# InkTime_NAN.net
KiCad netlist of a schematic drawn in EAGLE
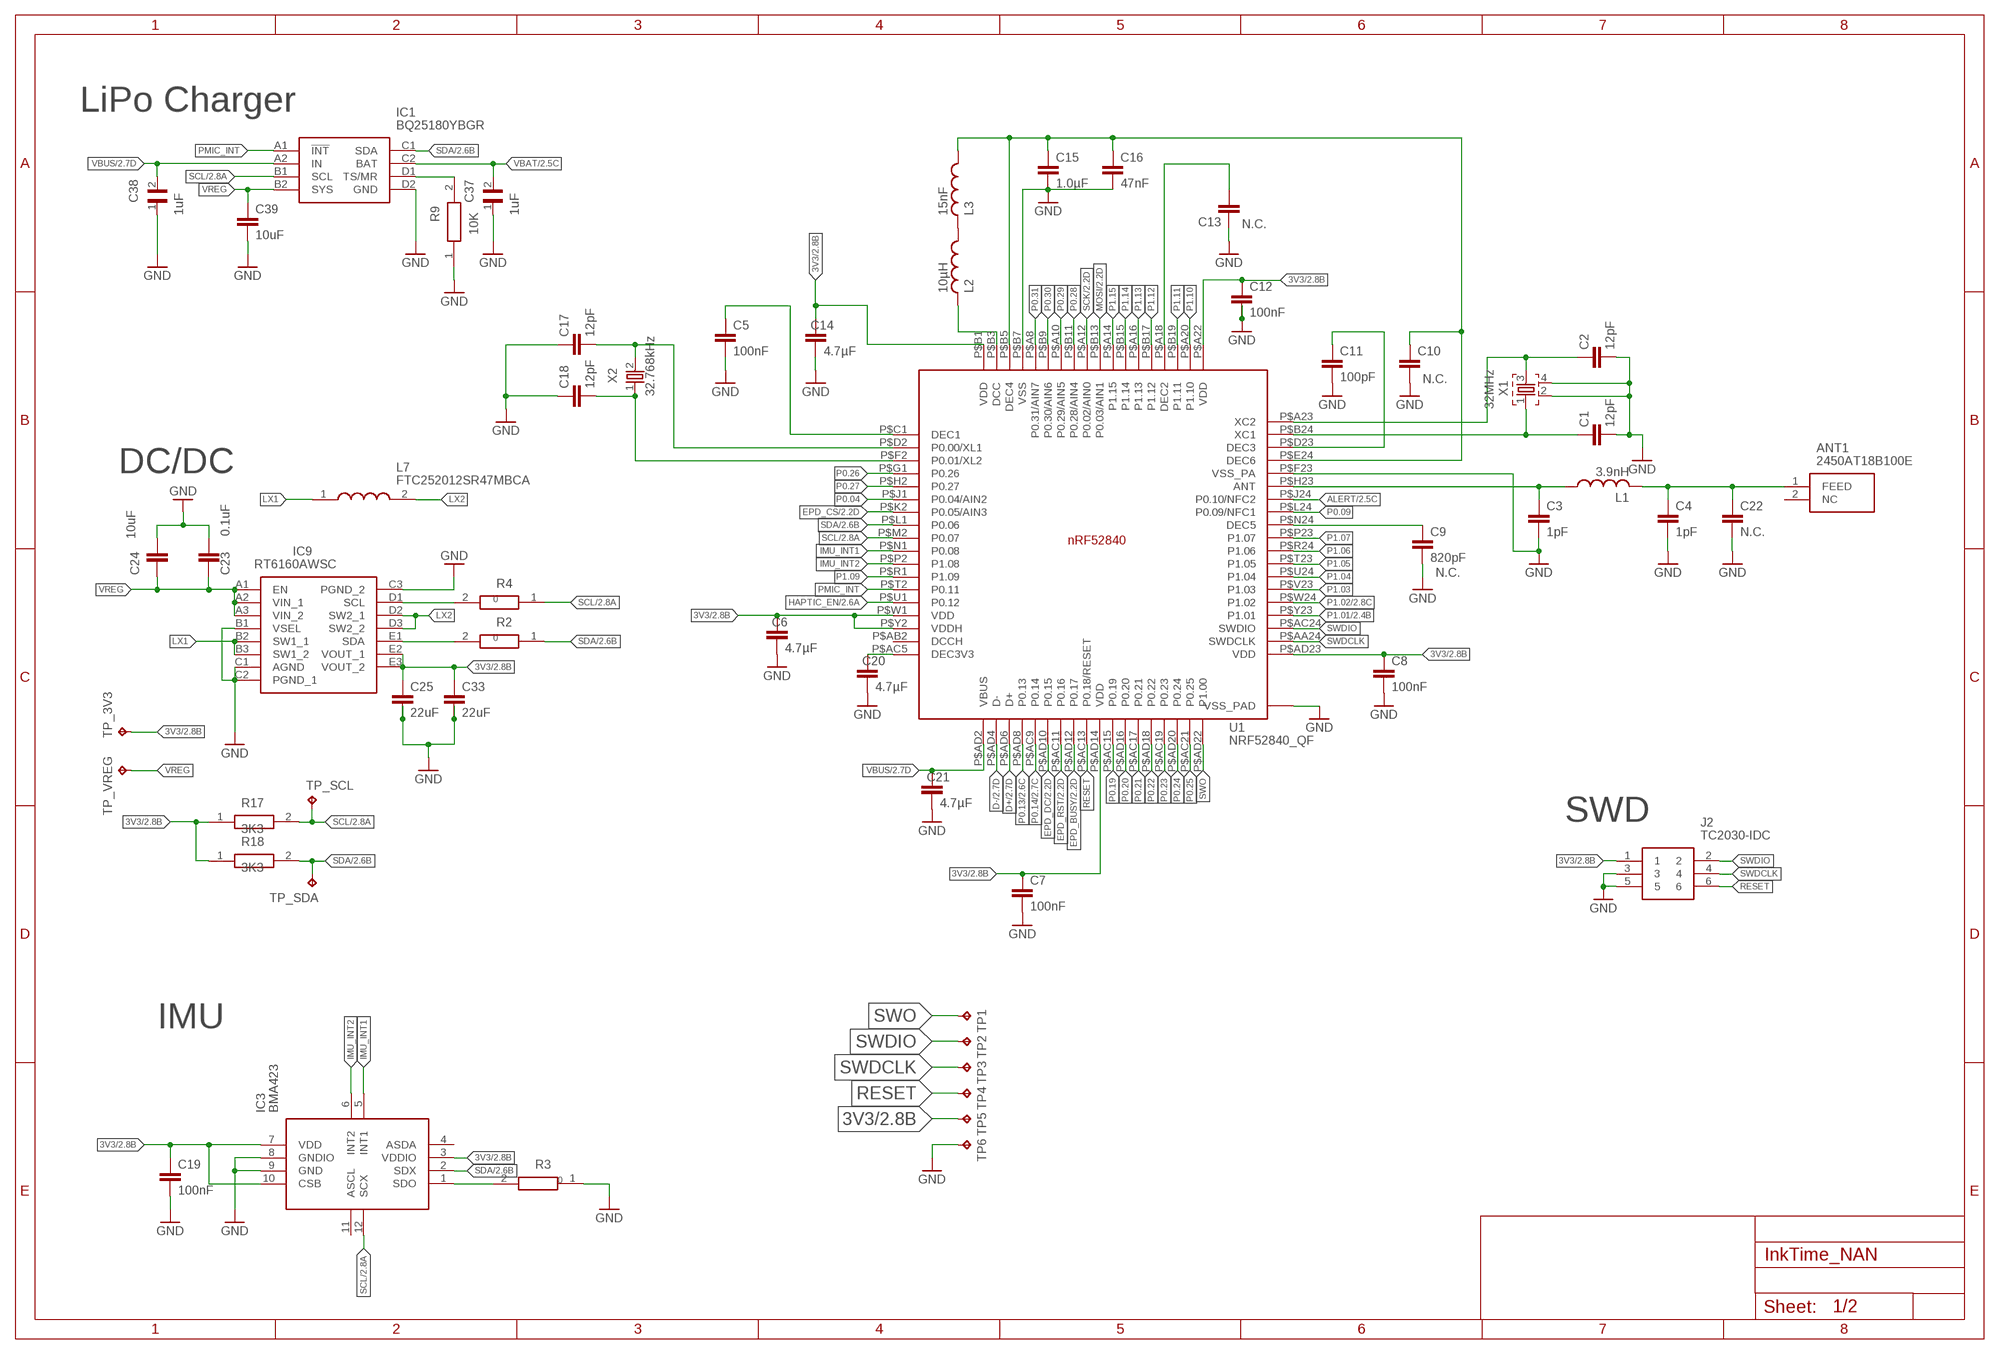
[diagram p0: schematic, sheet 1]
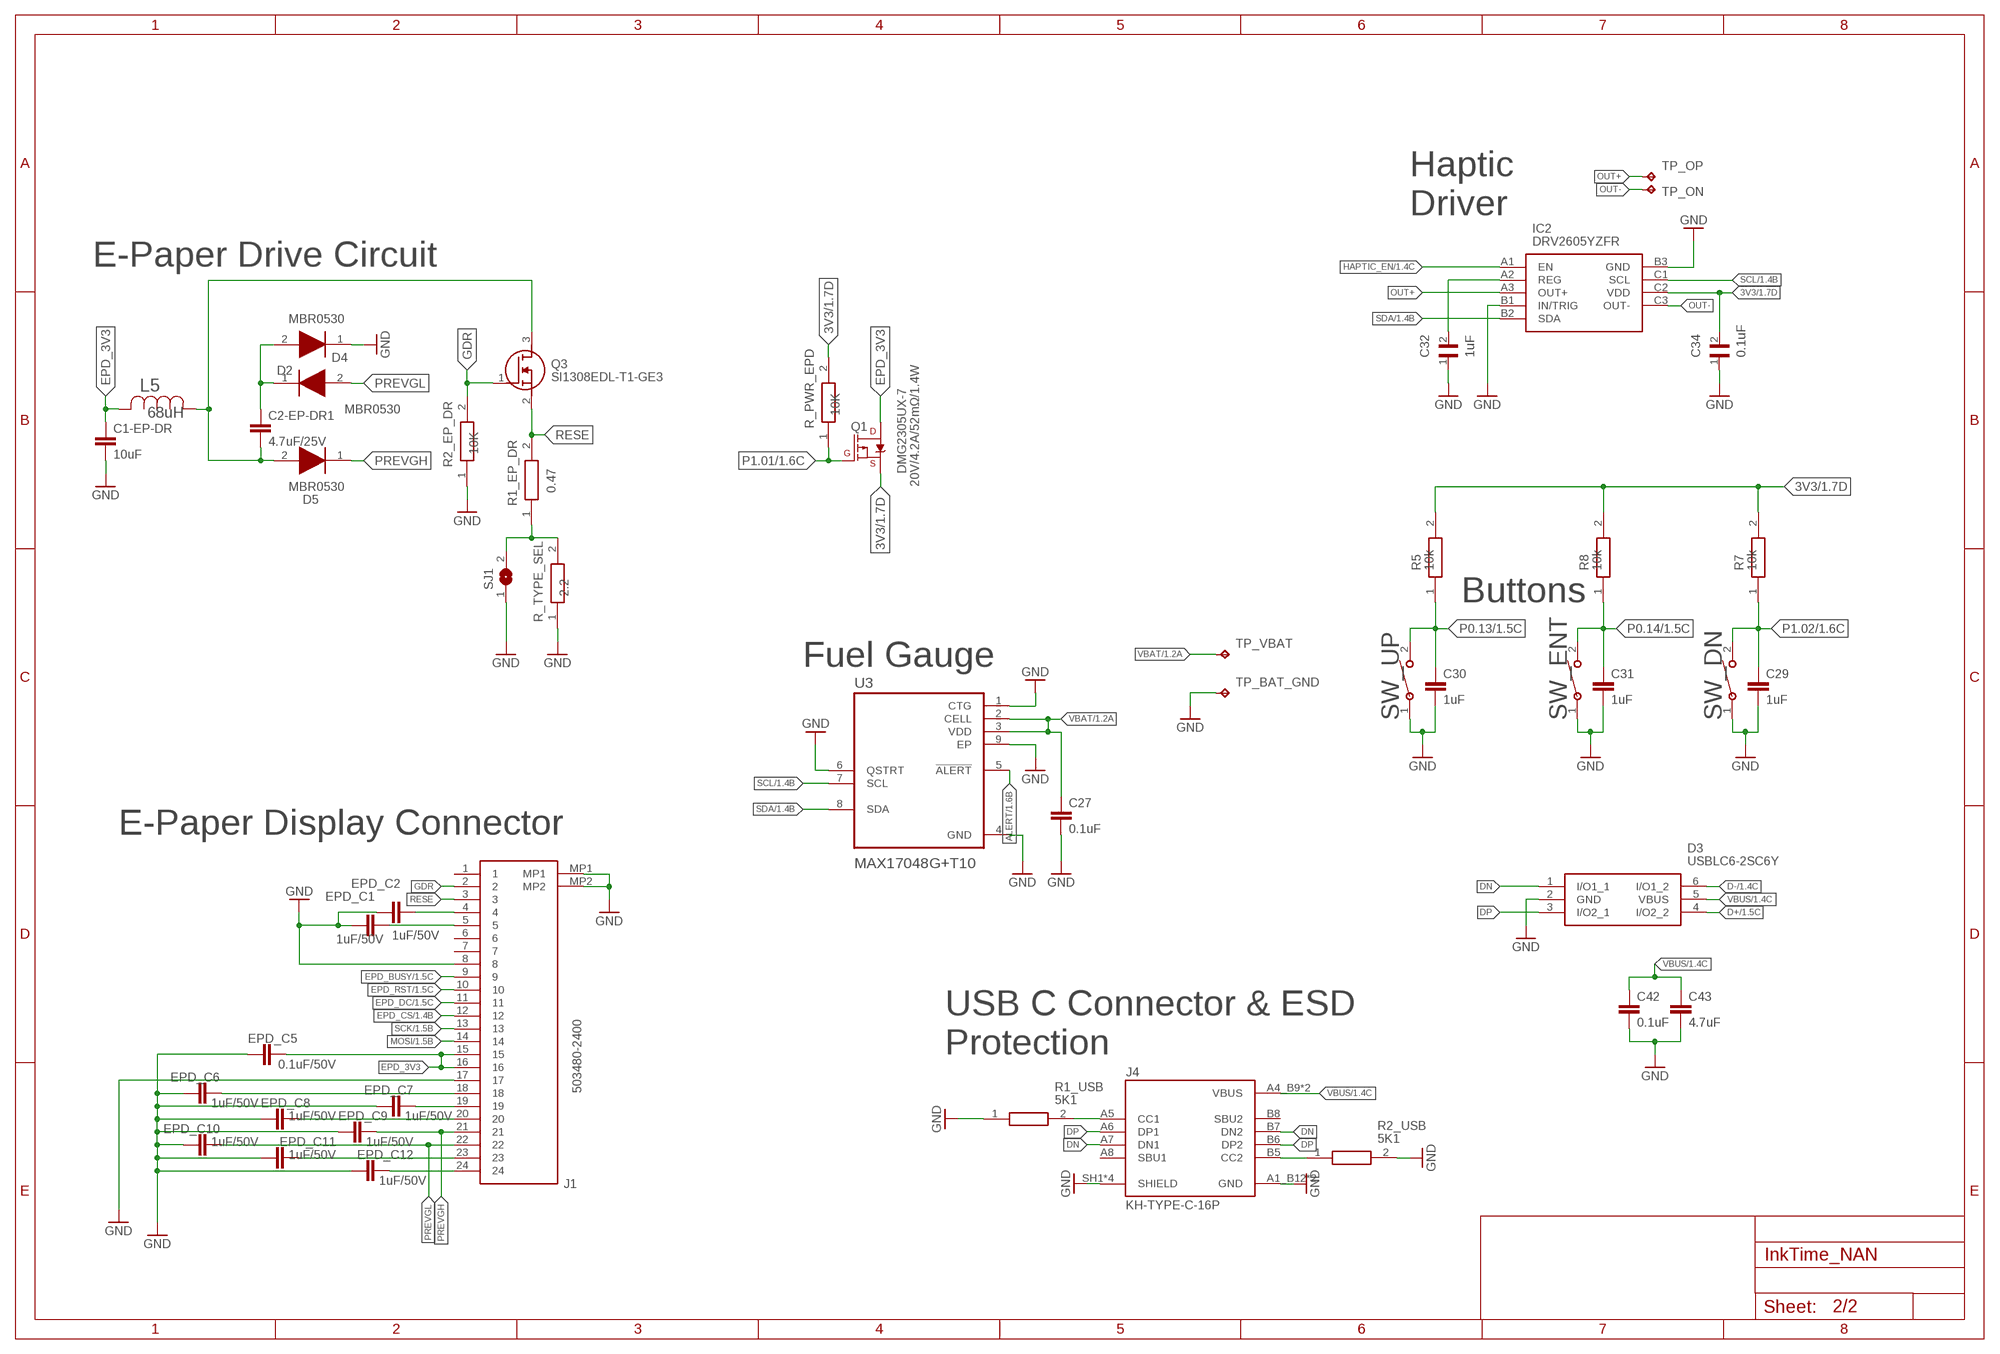
[diagram p1: schematic, sheet 2]

(export (version "E")
  (design (tool "Eeschema 10.0.6"))
  (components
    (comp (ref "C1-EP-DR")
      (value "10uF")
      (footprint "eagle-import:NORDIC_NRF_3_RESC0402_L")
      (libsource (lib "eagle-import") (part "NORDIC_NRF_3_CAPACITOR_0402_L"))
    )
    (comp (ref "C2-EP-DR1")
      (value "4.7uF/25V")
      (footprint "eagle-import:NORDIC_NRF_3_RESC0402_L")
      (libsource (lib "eagle-import") (part "NORDIC_NRF_3_CAPACITOR_0402_L"))
    )
    (comp (ref "C27")
      (value "0.1uF")
      (footprint "eagle-import:NORDIC_NRF_3_RESC0201_L")
      (libsource (lib "eagle-import") (part "NORDIC_NRF_3_CAPACITOR_0201_L"))
    )
    (comp (ref "C29")
      (value "1uF")
      (footprint "eagle-import:NORDIC_NRF_3_RESC0402_L")
      (libsource (lib "eagle-import") (part "NORDIC_NRF_3_CAPACITOR_0402_L"))
    )
    (comp (ref "C30")
      (value "1uF")
      (footprint "eagle-import:NORDIC_NRF_3_RESC0402_L")
      (libsource (lib "eagle-import") (part "NORDIC_NRF_3_CAPACITOR_0402_L"))
    )
    (comp (ref "C31")
      (value "1uF")
      (footprint "eagle-import:NORDIC_NRF_3_RESC0402_L")
      (libsource (lib "eagle-import") (part "NORDIC_NRF_3_CAPACITOR_0402_L"))
    )
    (comp (ref "C32")
      (value "1uF")
      (footprint "eagle-import:GRM011R60J152KE01L_2_CAPC0201X13N")
      (fields (field (name "MF") "Murata") (field (name "MP") "GRM011R60J152KE01L"))
      (libsource (lib "eagle-import") (part "GRM011R60J152KE01L_2_GRM011R60J152KE01L"))
    )
    (comp (ref "C34")
      (value "0.1uF")
      (footprint "eagle-import:GRM011R60J152KE01L_2_CAPC0201X13N")
      (fields (field (name "MF") "Murata") (field (name "MP") "GRM011R60J152KE01L"))
      (libsource (lib "eagle-import") (part "GRM011R60J152KE01L_2_GRM011R60J152KE01L"))
    )
    (comp (ref "C42")
      (value "0.1uF")
      (footprint "eagle-import:NORDIC_NRF_3_RESC0201_L")
      (libsource (lib "eagle-import") (part "NORDIC_NRF_3_CAPACITOR_0201_L"))
    )
    (comp (ref "C43")
      (value "4.7uF")
      (footprint "eagle-import:NORDIC_NRF_3_RESC0402_L")
      (libsource (lib "eagle-import") (part "NORDIC_NRF_3_CAPACITOR_0402_L"))
    )
    (comp (ref "D2")
      (value "MBR0530")
      (footprint "eagle-import:ESP32_C6_LIBRARY_5_SOD3716X135N")
      (fields (field (name "MF") "ON Semiconductor"))
      (libsource (lib "eagle-import") (part "ESP32_C6_LIBRARY_5_MBR0530"))
    )
    (comp (ref "D3")
      (value "USBLC6-2SC6Y")
      (footprint "eagle-import:ESP32_C6_LIBRARY_3_SOT95P280X145-6N")
      (fields (field (name "MF") "STMicroelectronics"))
      (libsource (lib "eagle-import") (part "ESP32_C6_LIBRARY_3_USBLC6-2SC6Y"))
    )
    (comp (ref "D4")
      (value "MBR0530")
      (footprint "eagle-import:ESP32_C6_LIBRARY_5_SOD3716X135N")
      (fields (field (name "MF") "ON Semiconductor"))
      (libsource (lib "eagle-import") (part "ESP32_C6_LIBRARY_5_MBR0530"))
    )
    (comp (ref "D5")
      (value "MBR0530")
      (footprint "eagle-import:ESP32_C6_LIBRARY_5_SOD3716X135N")
      (fields (field (name "MF") "ON Semiconductor"))
      (libsource (lib "eagle-import") (part "ESP32_C6_LIBRARY_5_MBR0530"))
    )
    (comp (ref "EPD_C1")
      (value "1uF/50V")
      (footprint "eagle-import:NORDIC_NRF_3_RESC0402_L")
      (libsource (lib "eagle-import") (part "NORDIC_NRF_3_CAPACITOR_0402_L"))
    )
    (comp (ref "EPD_C2")
      (value "1uF/50V")
      (footprint "eagle-import:NORDIC_NRF_3_RESC0402_L")
      (libsource (lib "eagle-import") (part "NORDIC_NRF_3_CAPACITOR_0402_L"))
    )
    (comp (ref "EPD_C5")
      (value "0.1uF/50V")
      (footprint "eagle-import:NORDIC_NRF_3_RESC0201_L")
      (libsource (lib "eagle-import") (part "NORDIC_NRF_3_CAPACITOR_0201_L"))
    )
    (comp (ref "EPD_C6")
      (value "1uF/50V")
      (footprint "eagle-import:NORDIC_NRF_3_RESC0402_L")
      (libsource (lib "eagle-import") (part "NORDIC_NRF_3_CAPACITOR_0402_L"))
    )
    (comp (ref "EPD_C7")
      (value "1uF/50V")
      (footprint "eagle-import:NORDIC_NRF_3_RESC0402_L")
      (libsource (lib "eagle-import") (part "NORDIC_NRF_3_CAPACITOR_0402_L"))
    )
    (comp (ref "EPD_C8")
      (value "1uF/50V")
      (footprint "eagle-import:NORDIC_NRF_3_RESC0402_L")
      (libsource (lib "eagle-import") (part "NORDIC_NRF_3_CAPACITOR_0402_L"))
    )
    (comp (ref "EPD_C9")
      (value "1uF/50V")
      (footprint "eagle-import:NORDIC_NRF_3_RESC0402_L")
      (libsource (lib "eagle-import") (part "NORDIC_NRF_3_CAPACITOR_0402_L"))
    )
    (comp (ref "EPD_C10")
      (value "1uF/50V")
      (footprint "eagle-import:NORDIC_NRF_3_RESC0402_L")
      (libsource (lib "eagle-import") (part "NORDIC_NRF_3_CAPACITOR_0402_L"))
    )
    (comp (ref "EPD_C11")
      (value "1uF/50V")
      (footprint "eagle-import:NORDIC_NRF_3_RESC0402_L")
      (libsource (lib "eagle-import") (part "NORDIC_NRF_3_CAPACITOR_0402_L"))
    )
    (comp (ref "EPD_C12")
      (value "1uF/50V")
      (footprint "eagle-import:NORDIC_NRF_3_RESC0402_L")
      (libsource (lib "eagle-import") (part "NORDIC_NRF_3_CAPACITOR_0402_L"))
    )
    (comp (ref "IC2")
      (value "DRV2605YZFR")
      (footprint "eagle-import:DRV2605YZFR_BGA9C50P3X3_144X144X62")
      (libsource (lib "eagle-import") (part "DRV2605YZFR_DRV2605YZFR"))
    )
    (comp (ref "J1")
      (value "503480-2400")
      (footprint "eagle-import:503480-2400_5034802400")
      (fields (field (name "MOUSER_PART_NUMBER") "538-503480-2400"))
      (libsource (lib "eagle-import") (part "503480-2400_503480-2400"))
    )
    (comp (ref "J4")
      (value "KH-TYPE-C-16P")
      (footprint "eagle-import:KH-TYPE-C-16P_KINGHELM_KH-TYPE-C-16P")
      (fields (field (name "MF") "kinghelm"))
      (libsource (lib "eagle-import") (part "KH-TYPE-C-16P_KH-TYPE-C-16P"))
    )
    (comp (ref "L5")
      (value "68uH")
      (footprint "eagle-import:ESP32_C6_LIBRARY_2_IND_4828-WE-TPC_WRE")
      (fields
        (field (name "MANUFACTURER_PART_NUMBER") "744043680")
        (field (name "COPYRIGHT") "Copyright (C) 2024 Ultra Librarian. All rights reserved.")
      )
      (libsource (lib "eagle-import") (part "ESP32_C6_LIBRARY_2_744043680IND_4828-WE-TPC_WRE"))
    )
    (comp (ref "Q1")
      (value "20V/4.2A/52mΩ/1.4W")
      (footprint "eagle-import:ESP32_C6_LIBRARY_4_ESP32_C6_LIBRARY_4_ESP32_C6_LIBRARY_4_ESP32_C6_LIBRARY_4_ESP32_WROVER_SPARKFUN-DISCRETESEMI_SOT23-3")
      (libsource (lib "eagle-import") (part "ESP32_C6_LIBRARY_4_ESP32_WROVER_SPARKFUN-DISCRETESEMI_MOSFET_PCH-DMG2305UX-7"))
    )
    (comp (ref "Q3")
      (value "SI1308EDL-T1-GE3")
      (footprint "eagle-import:ESP32_C6_LIBRARY_6_SOT65P210X110-3N")
      (fields (field (name "MF") "Vishay Siliconix"))
      (libsource (lib "eagle-import") (part "ESP32_C6_LIBRARY_6_SI1308EDL-T1-GE3"))
    )
    (comp (ref "R1_EP_DR")
      (value "0.47")
      (footprint "eagle-import:CPF0201D7K68C1_0201")
      (libsource (lib "eagle-import") (part "CPF0201D7K68C1_CPF0201D7K68C1"))
    )
    (comp (ref "R1_USB")
      (value "5K1")
      (footprint "eagle-import:ERA-1AEB3401C_0201")
      (libsource (lib "eagle-import") (part "ERA-1AEB3401C_CPF0201D7K68C1"))
    )
    (comp (ref "R2_EP_DR")
      (value "10K")
      (footprint "eagle-import:CPF0201D7K68C1_0201")
      (libsource (lib "eagle-import") (part "CPF0201D7K68C1_CPF0201D7K68C1"))
    )
    (comp (ref "R2_USB")
      (value "5K1")
      (footprint "eagle-import:ERA-1AEB3401C_0201")
      (libsource (lib "eagle-import") (part "ERA-1AEB3401C_CPF0201D7K68C1"))
    )
    (comp (ref "R5")
      (value "10k")
      (footprint "eagle-import:CPF0201D7K68C1_0201")
      (libsource (lib "eagle-import") (part "CPF0201D7K68C1_CPF0201D7K68C1"))
    )
    (comp (ref "R7")
      (value "10k")
      (footprint "eagle-import:CPF0201D7K68C1_0201")
      (libsource (lib "eagle-import") (part "CPF0201D7K68C1_CPF0201D7K68C1"))
    )
    (comp (ref "R8")
      (value "10k")
      (footprint "eagle-import:CPF0201D7K68C1_0201")
      (libsource (lib "eagle-import") (part "CPF0201D7K68C1_CPF0201D7K68C1"))
    )
    (comp (ref "R_PWR_EPD")
      (value "10K")
      (footprint "eagle-import:CPF0201D7K68C1_0201")
      (libsource (lib "eagle-import") (part "CPF0201D7K68C1_CPF0201D7K68C1"))
    )
    (comp (ref "R_TYPE_SEL")
      (value "2.2")
      (footprint "eagle-import:CPF0201D7K68C1_0201")
      (libsource (lib "eagle-import") (part "CPF0201D7K68C1_CPF0201D7K68C1"))
    )
    (comp (ref "SJ1")
      (value "ESP32_C6_LIBRARY_7_JUMPER_SJ")
      (footprint "eagle-import:ESP32_C6_LIBRARY_7_JUMPER_SJ")
      (libsource (lib "eagle-import") (part "ESP32_C6_LIBRARY_7_JUMPER_SJ"))
    )
    (comp (ref "SW_DN")
      (value "2025-10-22_07-23-44_LIBRARY_EVP-AKE31ASW_EVP-AKE31A_PAN")
      (footprint "eagle-import:2025-10-22_07-23-44_LIBRARY_SW_EVP-AKE31A_PAN")
      (fields
        (field (name "MANUFACTURER_PART_NUMBER") "EVP-AKE31A")
        (field (name "COPYRIGHT") "Copyright (C) 2025 Ultra Librarian. All rights reserved.")
      )
      (libsource (lib "eagle-import") (part "2025-10-22_07-23-44_LIBRARY_EVP-AKE31ASW_EVP-AKE31A_PAN"))
    )
    (comp (ref "SW_ENT")
      (value "SW_ENT")
      (footprint "eagle-import:2025-10-22_07-23-44_LIBRARY_SW_EVP-AKE31A_PAN")
      (fields
        (field (name "MANUFACTURER_PART_NUMBER") "EVP-AKE31A")
        (field (name "COPYRIGHT") "Copyright (C) 2025 Ultra Librarian. All rights reserved.")
      )
      (libsource (lib "eagle-import") (part "2025-10-22_07-23-44_LIBRARY_EVP-AKE31ASW_EVP-AKE31A_PAN"))
    )
    (comp (ref "SW_UP")
      (value "2025-10-22_07-23-44_LIBRARY_EVP-AKE31ASW_EVP-AKE31A_PAN")
      (footprint "eagle-import:2025-10-22_07-23-44_LIBRARY_SW_EVP-AKE31A_PAN")
      (fields
        (field (name "MANUFACTURER_PART_NUMBER") "EVP-AKE31A")
        (field (name "COPYRIGHT") "Copyright (C) 2025 Ultra Librarian. All rights reserved.")
      )
      (libsource (lib "eagle-import") (part "2025-10-22_07-23-44_LIBRARY_EVP-AKE31ASW_EVP-AKE31A_PAN"))
    )
    (comp (ref "TP_BAT_GND")
      (value "HECTOR_WATCH_1_TPTP20R")
      (footprint "eagle-import:HECTOR_WATCH_1_TP20R")
      (libsource (lib "eagle-import") (part "HECTOR_WATCH_1_TPTP20R"))
    )
    (comp (ref "TP_ON")
      (value "HECTOR_WATCH_1_TPTP20R")
      (footprint "eagle-import:HECTOR_WATCH_1_TP20R")
      (libsource (lib "eagle-import") (part "HECTOR_WATCH_1_TPTP20R"))
    )
    (comp (ref "TP_OP")
      (value "HECTOR_WATCH_1_TPTP20R")
      (footprint "eagle-import:HECTOR_WATCH_1_TP20R")
      (libsource (lib "eagle-import") (part "HECTOR_WATCH_1_TPTP20R"))
    )
    (comp (ref "TP_VBAT")
      (value "HECTOR_WATCH_1_TPTP20R")
      (footprint "eagle-import:HECTOR_WATCH_1_TP20R")
      (libsource (lib "eagle-import") (part "HECTOR_WATCH_1_TPTP20R"))
    )
    (comp (ref "U3")
      (value "MAX17048G+T10")
      (footprint "eagle-import:ESP32_C6_LIBRARY_SON50P200X200X80-9N")
      (fields (field (name "MF") "Analog Devices"))
      (libsource (lib "eagle-import") (part "ESP32_C6_LIBRARY_MAX17048G+T10"))
    )
    (comp (ref "ANT1")
      (value "2450AT18B100E")
      (footprint "eagle-import:2450AT18B100E_ANTC3216X140N")
      (fields (field (name "MOUSER_PART_NUMBER") "609-2450AT18B100E"))
      (libsource (lib "eagle-import") (part "2450AT18B100E_2450AT18B100E"))
    )
    (comp (ref "C1")
      (value "12pF")
      (footprint "eagle-import:NORDIC_NRF_3_RESC0201_L")
      (libsource (lib "eagle-import") (part "NORDIC_NRF_3_CAPACITOR_0201_L"))
    )
    (comp (ref "C2")
      (value "12pF")
      (footprint "eagle-import:NORDIC_NRF_3_RESC0201_L")
      (libsource (lib "eagle-import") (part "NORDIC_NRF_3_CAPACITOR_0201_L"))
    )
    (comp (ref "C3")
      (value "1pF")
      (footprint "eagle-import:NORDIC_NRF_3_RESC0201_L")
      (libsource (lib "eagle-import") (part "NORDIC_NRF_3_CAPACITOR_0201_L"))
    )
    (comp (ref "C4")
      (value "1pF")
      (footprint "eagle-import:NORDIC_NRF_3_RESC0201_L")
      (libsource (lib "eagle-import") (part "NORDIC_NRF_3_CAPACITOR_0201_L"))
    )
    (comp (ref "C5")
      (value "100nF")
      (footprint "eagle-import:NORDIC_NRF_3_RESC0201_L")
      (libsource (lib "eagle-import") (part "NORDIC_NRF_3_CAPACITOR_0201_L"))
    )
    (comp (ref "C6")
      (value "4.7µF")
      (footprint "eagle-import:NORDIC_NRF_3_RESC0402_L")
      (libsource (lib "eagle-import") (part "NORDIC_NRF_3_CAPACITOR_0402_L"))
    )
    (comp (ref "C7")
      (value "100nF")
      (footprint "eagle-import:NORDIC_NRF_3_RESC0201_L")
      (libsource (lib "eagle-import") (part "NORDIC_NRF_3_CAPACITOR_0201_L"))
    )
    (comp (ref "C8")
      (value "100nF")
      (footprint "eagle-import:NORDIC_NRF_3_RESC0201_L")
      (libsource (lib "eagle-import") (part "NORDIC_NRF_3_CAPACITOR_0201_L"))
    )
    (comp (ref "C9")
      (value "820pF")
      (footprint "eagle-import:NORDIC_NRF_3_RESC0201_L")
      (libsource (lib "eagle-import") (part "NORDIC_NRF_3_CAPACITOR_0201_L"))
    )
    (comp (ref "C10")
      (value "NORDIC_NRF_3_CAPACITOR_0201_L")
      (footprint "eagle-import:NORDIC_NRF_3_RESC0201_L")
      (libsource (lib "eagle-import") (part "NORDIC_NRF_3_CAPACITOR_0201_L"))
    )
    (comp (ref "C11")
      (value "100pF")
      (footprint "eagle-import:NORDIC_NRF_3_RESC0201_L")
      (libsource (lib "eagle-import") (part "NORDIC_NRF_3_CAPACITOR_0201_L"))
    )
    (comp (ref "C12")
      (value "100nF")
      (footprint "eagle-import:NORDIC_NRF_3_RESC0201_L")
      (libsource (lib "eagle-import") (part "NORDIC_NRF_3_CAPACITOR_0201_L"))
    )
    (comp (ref "C13")
      (value "NORDIC_NRF_3_CAPACITOR_0201_L")
      (footprint "eagle-import:NORDIC_NRF_3_RESC0201_L")
      (libsource (lib "eagle-import") (part "NORDIC_NRF_3_CAPACITOR_0201_L"))
    )
    (comp (ref "C14")
      (value "4.7µF")
      (footprint "eagle-import:NORDIC_NRF_3_RESC0402_L")
      (libsource (lib "eagle-import") (part "NORDIC_NRF_3_CAPACITOR_0402_L"))
    )
    (comp (ref "C15")
      (value "1.0µF")
      (footprint "eagle-import:NORDIC_NRF_3_RESC0402_L")
      (libsource (lib "eagle-import") (part "NORDIC_NRF_3_CAPACITOR_0402_L"))
    )
    (comp (ref "C16")
      (value "47nF")
      (footprint "eagle-import:NORDIC_NRF_3_RESC0201_L")
      (libsource (lib "eagle-import") (part "NORDIC_NRF_3_CAPACITOR_0201_L"))
    )
    (comp (ref "C17")
      (value "12pF")
      (footprint "eagle-import:NORDIC_NRF_3_RESC0201_L")
      (libsource (lib "eagle-import") (part "NORDIC_NRF_3_CAPACITOR_0201_L"))
    )
    (comp (ref "C18")
      (value "12pF")
      (footprint "eagle-import:NORDIC_NRF_3_RESC0201_L")
      (libsource (lib "eagle-import") (part "NORDIC_NRF_3_CAPACITOR_0201_L"))
    )
    (comp (ref "C19")
      (value "100nF")
      (footprint "eagle-import:NORDIC_NRF_3_RESC0201_L")
      (libsource (lib "eagle-import") (part "InkTime_v5_vf.fkz7WSyWSr61TWkXU9X4_w_NORDIC_NRF_3_CAPACITOR_0201_L"))
    )
    (comp (ref "C20")
      (value "4.7µF")
      (footprint "eagle-import:NORDIC_NRF_3_RESC0402_L")
      (libsource (lib "eagle-import") (part "NORDIC_NRF_3_CAPACITOR_0402_L"))
    )
    (comp (ref "C21")
      (value "4.7µF")
      (footprint "eagle-import:NORDIC_NRF_3_RESC0402_L")
      (libsource (lib "eagle-import") (part "NORDIC_NRF_3_CAPACITOR_0402_L"))
    )
    (comp (ref "C22")
      (value "N.C.")
      (footprint "eagle-import:NORDIC_NRF_3_RESC0201_L")
      (libsource (lib "eagle-import") (part "NORDIC_NRF_3_CAPACITOR_0201_L"))
    )
    (comp (ref "C23")
      (value "0.1uF")
      (footprint "eagle-import:NORDIC_NRF_3_RESC0201_L")
      (libsource (lib "eagle-import") (part "InkTime_v5_vf.fkz7WSyWSr61TWkXU9X4_w_NORDIC_NRF_3_CAPACITOR_0201_L"))
    )
    (comp (ref "C24")
      (value "10uF")
      (footprint "eagle-import:NORDIC_NRF_3_RESC0402_L")
      (libsource (lib "eagle-import") (part "NORDIC_NRF_3_CAPACITOR_0402_L"))
    )
    (comp (ref "C25")
      (value "22uF")
      (footprint "eagle-import:NORDIC_NRF_3_RESC0402_L")
      (libsource (lib "eagle-import") (part "NORDIC_NRF_3_CAPACITOR_0402_L"))
    )
    (comp (ref "C33")
      (value "22uF")
      (footprint "eagle-import:NORDIC_NRF_3_RESC0402_L")
      (libsource (lib "eagle-import") (part "NORDIC_NRF_3_CAPACITOR_0402_L"))
    )
    (comp (ref "C37")
      (value "1uF")
      (footprint "eagle-import:GRM011R60J152KE01L_2_CAPC0201X13N")
      (fields (field (name "MF") "Murata") (field (name "MP") "GRM011R60J152KE01L"))
      (libsource (lib "eagle-import") (part "GRM011R60J152KE01L_2_GRM011R60J152KE01L"))
    )
    (comp (ref "C38")
      (value "1uF")
      (footprint "eagle-import:GRM011R60J152KE01L_2_CAPC0201X13N")
      (fields (field (name "MF") "Murata") (field (name "MP") "GRM011R60J152KE01L"))
      (libsource (lib "eagle-import") (part "GRM011R60J152KE01L_2_GRM011R60J152KE01L"))
    )
    (comp (ref "C39")
      (value "10uF")
      (footprint "eagle-import:NORDIC_NRF_3_RESC0402_L")
      (libsource (lib "eagle-import") (part "NORDIC_NRF_3_CAPACITOR_0402_L"))
    )
    (comp (ref "IC1")
      (value "BQ25180YBGR")
      (footprint "eagle-import:BQ25180YBGR_BGA8C40P2X4_100X155X50")
      (fields (field (name "MOUSER_PART_NUMBER") "595-BQ25180YBGR"))
      (libsource (lib "eagle-import") (part "BQ25180YBGR_BQ25180YBGR"))
    )
    (comp (ref "IC3")
      (value "BMA423")
      (footprint "eagle-import:BMA423_BMA423")
      (fields (field (name "MOUSER_PART_NUMBER") "262-BMA423"))
      (libsource (lib "eagle-import") (part "BMA423_BMA423"))
    )
    (comp (ref "IC9")
      (value "RT6160AWSC")
      (footprint "eagle-import:RT6160AWSC_BGA15C40P3X5_140X230X60")
      (fields (field (name "MOUSER_PART_NUMBER") "835-RT6160AWSC"))
      (libsource (lib "eagle-import") (part "RT6160AWSC_RT6160AWSC"))
    )
    (comp (ref "J2")
      (value "TC2030-IDC")
      (footprint "eagle-import:TC2030-IDC_TC2030IDC")
      (libsource (lib "eagle-import") (part "TC2030-IDC_TC2030-IDC"))
    )
    (comp (ref "L1")
      (value "3.9nH")
      (footprint "eagle-import:NORDIC_NRF_2_RESC0402_L")
      (libsource (lib "eagle-import") (part "InkTime_v5_vf.fkz7WSyWSr61TWkXU9X4_w_NORDIC_NRF_2_INDUCTOR_0402_L"))
    )
    (comp (ref "L2")
      (value "10µH")
      (footprint "eagle-import:NORDIC_NRF_2_RESC0402_L")
      (libsource (lib "eagle-import") (part "NORDIC_NRF_2_INDUCTOR_0402_L"))
    )
    (comp (ref "L3")
      (value "15nF")
      (footprint "eagle-import:NORDIC_NRF_2_RESC0402_L")
      (libsource (lib "eagle-import") (part "NORDIC_NRF_2_INDUCTOR_0402_L"))
    )
    (comp (ref "L7")
      (value "FTC252012SR47MBCA")
      (footprint "eagle-import:MLP2016SR47MT0S1_INDC2016X100N")
      (libsource (lib "eagle-import") (part "MLP2016SR47MT0S1_FTC252012SR47MBCA"))
    )
    (comp (ref "R2")
      (value "CPF0201D7K68C1_CPF0201D7K68C1")
      (footprint "eagle-import:CPF0201D7K68C1_0201")
      (libsource (lib "eagle-import") (part "CPF0201D7K68C1_CPF0201D7K68C1"))
    )
    (comp (ref "R3")
      (value "CPF0201D7K68C1_CPF0201D7K68C1")
      (footprint "eagle-import:CPF0201D7K68C1_0201")
      (libsource (lib "eagle-import") (part "CPF0201D7K68C1_CPF0201D7K68C1"))
    )
    (comp (ref "R4")
      (value "CPF0201D7K68C1_CPF0201D7K68C1")
      (footprint "eagle-import:CPF0201D7K68C1_0201")
      (libsource (lib "eagle-import") (part "CPF0201D7K68C1_CPF0201D7K68C1"))
    )
    (comp (ref "R9")
      (value "10K")
      (footprint "eagle-import:CPF0201D7K68C1_0201")
      (libsource (lib "eagle-import") (part "CPF0201D7K68C1_CPF0201D7K68C1"))
    )
    (comp (ref "R17")
      (value "3K3")
      (footprint "eagle-import:CPF0201D7K68C1_0201")
      (libsource (lib "eagle-import") (part "CPF0201D7K68C1_CPF0201D7K68C1"))
    )
    (comp (ref "R18")
      (value "3K3")
      (footprint "eagle-import:CPF0201D7K68C1_0201")
      (libsource (lib "eagle-import") (part "CPF0201D7K68C1_CPF0201D7K68C1"))
    )
    (comp (ref "TP1")
      (value "HECTOR_WATCH_1_TPTP20R")
      (footprint "eagle-import:HECTOR_WATCH_1_TP20R")
      (libsource (lib "eagle-import") (part "HECTOR_WATCH_1_TPTP20R"))
    )
    (comp (ref "TP2")
      (value "HECTOR_WATCH_1_TPTP20R")
      (footprint "eagle-import:HECTOR_WATCH_1_TP20R")
      (libsource (lib "eagle-import") (part "HECTOR_WATCH_1_TPTP20R"))
    )
    (comp (ref "TP3")
      (value "HECTOR_WATCH_1_TPTP20R")
      (footprint "eagle-import:HECTOR_WATCH_1_TP20R")
      (libsource (lib "eagle-import") (part "HECTOR_WATCH_1_TPTP20R"))
    )
    (comp (ref "TP4")
      (value "HECTOR_WATCH_1_TPTP20R")
      (footprint "eagle-import:HECTOR_WATCH_1_TP20R")
      (libsource (lib "eagle-import") (part "HECTOR_WATCH_1_TPTP20R"))
    )
    (comp (ref "TP5")
      (value "HECTOR_WATCH_1_TPTP20R")
      (footprint "eagle-import:HECTOR_WATCH_1_TP20R")
      (libsource (lib "eagle-import") (part "HECTOR_WATCH_1_TPTP20R"))
    )
    (comp (ref "TP6")
      (value "HECTOR_WATCH_1_TPTP20R")
      (footprint "eagle-import:HECTOR_WATCH_1_TP20R")
      (libsource (lib "eagle-import") (part "HECTOR_WATCH_1_TPTP20R"))
    )
    (comp (ref "TP_3V3")
      (value "HECTOR_WATCH_1_TPTP20R")
      (footprint "eagle-import:HECTOR_WATCH_1_TP20R")
      (libsource (lib "eagle-import") (part "HECTOR_WATCH_1_TPTP20R"))
    )
    (comp (ref "TP_SCL")
      (value "HECTOR_WATCH_1_TPTP20R")
      (footprint "eagle-import:HECTOR_WATCH_1_TP20R")
      (libsource (lib "eagle-import") (part "HECTOR_WATCH_1_TPTP20R"))
    )
    (comp (ref "TP_SDA")
      (value "HECTOR_WATCH_1_TPTP20R")
      (footprint "eagle-import:HECTOR_WATCH_1_TP20R")
      (libsource (lib "eagle-import") (part "HECTOR_WATCH_1_TPTP20R"))
    )
    (comp (ref "TP_VREG")
      (value "HECTOR_WATCH_1_TPTP20R")
      (footprint "eagle-import:HECTOR_WATCH_1_TP20R")
      (libsource (lib "eagle-import") (part "HECTOR_WATCH_1_TPTP20R"))
    )
    (comp (ref "U1")
      (value "NRF52840_QF")
      (footprint "eagle-import:NORDIC_NRF_4_AQFN50P700X700X85_HS-74N")
      (libsource (lib "eagle-import") (part "NORDIC_NRF_4_NRF52840_QF"))
    )
    (comp (ref "X1")
      (value "32MHz")
      (footprint "eagle-import:NORDIC_NRF_BT-XTAL_2016_N")
      (libsource (lib "eagle-import") (part "NORDIC_NRF_XTAL_32MHZ"))
    )
    (comp (ref "X2")
      (value "32.768kHz")
      (footprint "eagle-import:NORDIC_NRF_1_XTAL_3215_N")
      (libsource (lib "eagle-import") (part "NORDIC_NRF_1_XTAL_32KHZ"))
    )
  )
  (nets
    (net (code "1") (name "3V3") (class "Default")
      (node (ref "C12") (pin "1") (pinfunction "1_1") (pintype "passive"))
      (node (ref "C14") (pin "1") (pinfunction "1_1") (pintype "passive"))
      (node (ref "C19") (pin "1") (pinfunction "1_1") (pintype "passive"))
      (node (ref "C25") (pin "1") (pinfunction "1_1") (pintype "passive"))
      (node (ref "C33") (pin "1") (pinfunction "1_1") (pintype "passive"))
      (node (ref "C34") (pin "2") (pinfunction "2_2") (pintype "passive"))
      (node (ref "C6") (pin "1") (pinfunction "1_1") (pintype "passive"))
      (node (ref "C7") (pin "1") (pinfunction "1_1") (pintype "passive"))
      (node (ref "C8") (pin "1") (pinfunction "1_1") (pintype "passive"))
      (node (ref "IC2") (pin "C2") (pinfunction "VDD_C2") (pintype "bidirectional"))
      (node (ref "IC3") (pin "10") (pinfunction "CSB_10") (pintype "bidirectional"))
      (node (ref "IC3") (pin "3") (pinfunction "VDDIO_3") (pintype "bidirectional"))
      (node (ref "IC3") (pin "7") (pinfunction "VDD_7") (pintype "bidirectional"))
      (node (ref "IC9") (pin "E2") (pinfunction "VOUT_1_E2") (pintype "bidirectional"))
      (node (ref "IC9") (pin "E3") (pinfunction "VOUT_2_E3") (pintype "bidirectional"))
      (node (ref "J2") (pin "1") (pinfunction "1_1") (pintype "bidirectional"))
      (node (ref "Q1") (pin "2") (pinfunction "S_2") (pintype "bidirectional"))
      (node (ref "R17") (pin "1") (pinfunction "1_1") (pintype "bidirectional"))
      (node (ref "R18") (pin "1") (pinfunction "1_1") (pintype "bidirectional"))
      (node (ref "R5") (pin "2") (pinfunction "2_2") (pintype "bidirectional"))
      (node (ref "R7") (pin "2") (pinfunction "2_2") (pintype "bidirectional"))
      (node (ref "R8") (pin "2") (pinfunction "2_2") (pintype "bidirectional"))
      (node (ref "R_PWR_EPD") (pin "2") (pinfunction "2_2") (pintype "bidirectional"))
      (node (ref "TP5") (pin "TP") (pinfunction "TP_TP") (pintype "input"))
      (node (ref "TP_3V3") (pin "TP") (pinfunction "TP_TP") (pintype "input"))
      (node (ref "U1") (pin "P$A22") (pinfunction "VDD_P$A22") (pintype "power_in"))
      (node (ref "U1") (pin "P$AD14") (pinfunction "VDD_P$AD14") (pintype "power_in"))
      (node (ref "U1") (pin "P$AD23") (pinfunction "VDD_P$AD23") (pintype "power_in"))
      (node (ref "U1") (pin "P$B1") (pinfunction "VDD_P$B1") (pintype "power_in"))
      (node (ref "U1") (pin "P$W1") (pinfunction "VDD_P$W1") (pintype "power_in"))
      (node (ref "U1") (pin "P$Y2") (pinfunction "VDDH_P$Y2") (pintype "power_in"))
    )
    (net (code "2") (name "ALERT") (class "Default")
      (node (ref "U1") (pin "P$J24") (pinfunction "P0.10/NFC2_P$J24") (pintype "bidirectional"))
      (node (ref "U3") (pin "5") (pinfunction "~{ALERT}_5") (pintype "output"))
    )
    (net (code "3") (name "D+") (class "Default")
      (node (ref "D3") (pin "4") (pinfunction "I/O2_2_4") (pintype "bidirectional"))
      (node (ref "U1") (pin "P$AD6") (pinfunction "D+_P$AD6") (pintype "bidirectional"))
    )
    (net (code "4") (name "D-") (class "Default")
      (node (ref "D3") (pin "6") (pinfunction "I/O1_2_6") (pintype "bidirectional"))
      (node (ref "U1") (pin "P$AD4") (pinfunction "D-_P$AD4") (pintype "bidirectional"))
    )
    (net (code "5") (name "DN") (class "Default")
      (node (ref "D3") (pin "1") (pinfunction "I/O1_1_1") (pintype "bidirectional"))
      (node (ref "J4") (pin "A7") (pinfunction "DN1_A7") (pintype "bidirectional"))
      (node (ref "J4") (pin "B7") (pinfunction "DN2_B7") (pintype "bidirectional"))
    )
    (net (code "6") (name "DP") (class "Default")
      (node (ref "D3") (pin "3") (pinfunction "I/O2_1_3") (pintype "bidirectional"))
      (node (ref "J4") (pin "A6") (pinfunction "DP1_A6") (pintype "bidirectional"))
      (node (ref "J4") (pin "B6") (pinfunction "DP2_B6") (pintype "bidirectional"))
    )
    (net (code "7") (name "EPD_3V3") (class "Default")
      (node (ref "C1-EP-DR") (pin "1") (pinfunction "1_1") (pintype "passive"))
      (node (ref "EPD_C5") (pin "2") (pinfunction "2_2") (pintype "passive"))
      (node (ref "J1") (pin "15") (pinfunction "15_15") (pintype "bidirectional"))
      (node (ref "J1") (pin "16") (pinfunction "16_16") (pintype "bidirectional"))
      (node (ref "L5") (pin "2") (pinfunction "2_2") (pintype "passive"))
      (node (ref "Q1") (pin "3") (pinfunction "D_3") (pintype "bidirectional"))
    )
    (net (code "8") (name "EPD_BUSY") (class "Default")
      (node (ref "J1") (pin "9") (pinfunction "9_9") (pintype "bidirectional"))
      (node (ref "U1") (pin "P$AD12") (pinfunction "P0.17_P$AD12") (pintype "bidirectional"))
    )
    (net (code "9") (name "EPD_CS") (class "Default")
      (node (ref "J1") (pin "12") (pinfunction "12_12") (pintype "bidirectional"))
      (node (ref "U1") (pin "P$K2") (pinfunction "P0.05/AIN3_P$K2") (pintype "bidirectional"))
    )
    (net (code "10") (name "EPD_DC") (class "Default")
      (node (ref "J1") (pin "11") (pinfunction "11_11") (pintype "bidirectional"))
      (node (ref "U1") (pin "P$AD10") (pinfunction "P0.15_P$AD10") (pintype "bidirectional"))
    )
    (net (code "11") (name "EPD_RST") (class "Default")
      (node (ref "J1") (pin "10") (pinfunction "10_10") (pintype "bidirectional"))
      (node (ref "U1") (pin "P$AC11") (pinfunction "P0.16_P$AC11") (pintype "bidirectional"))
    )
    (net (code "12") (name "GDR") (class "Default")
      (node (ref "J1") (pin "2") (pinfunction "2_2") (pintype "bidirectional"))
      (node (ref "Q3") (pin "1") (pinfunction "G_1") (pintype "bidirectional"))
      (node (ref "R2_EP_DR") (pin "2") (pinfunction "2_2") (pintype "bidirectional"))
    )
    (net (code "13") (name "GND") (class "Default")
      (node (ref "C1") (pin "2") (pinfunction "2_2") (pintype "passive"))
      (node (ref "C1-EP-DR") (pin "2") (pinfunction "2_2") (pintype "passive"))
      (node (ref "C10") (pin "1") (pinfunction "1_1") (pintype "passive"))
      (node (ref "C11") (pin "2") (pinfunction "2_2") (pintype "passive"))
      (node (ref "C12") (pin "2") (pinfunction "2_2") (pintype "passive"))
      (node (ref "C13") (pin "1") (pinfunction "1_1") (pintype "passive"))
      (node (ref "C14") (pin "2") (pinfunction "2_2") (pintype "passive"))
      (node (ref "C15") (pin "2") (pinfunction "2_2") (pintype "passive"))
      (node (ref "C16") (pin "2") (pinfunction "2_2") (pintype "passive"))
      (node (ref "C17") (pin "1") (pinfunction "1_1") (pintype "passive"))
      (node (ref "C18") (pin "1") (pinfunction "1_1") (pintype "passive"))
      (node (ref "C19") (pin "2") (pinfunction "2_2") (pintype "passive"))
      (node (ref "C2") (pin "2") (pinfunction "2_2") (pintype "passive"))
      (node (ref "C20") (pin "2") (pinfunction "2_2") (pintype "passive"))
      (node (ref "C21") (pin "2") (pinfunction "2_2") (pintype "passive"))
      (node (ref "C22") (pin "2") (pinfunction "2_2") (pintype "passive"))
      (node (ref "C23") (pin "1") (pinfunction "1_1") (pintype "passive"))
      (node (ref "C24") (pin "1") (pinfunction "1_1") (pintype "passive"))
      (node (ref "C25") (pin "2") (pinfunction "2_2") (pintype "passive"))
      (node (ref "C27") (pin "2") (pinfunction "2_2") (pintype "passive"))
      (node (ref "C29") (pin "2") (pinfunction "2_2") (pintype "passive"))
      (node (ref "C3") (pin "2") (pinfunction "2_2") (pintype "passive"))
      (node (ref "C30") (pin "2") (pinfunction "2_2") (pintype "passive"))
      (node (ref "C31") (pin "2") (pinfunction "2_2") (pintype "passive"))
      (node (ref "C32") (pin "1") (pinfunction "1_1") (pintype "passive"))
      (node (ref "C33") (pin "2") (pinfunction "2_2") (pintype "passive"))
      (node (ref "C34") (pin "1") (pinfunction "1_1") (pintype "passive"))
      (node (ref "C37") (pin "1") (pinfunction "1_1") (pintype "passive"))
      (node (ref "C38") (pin "1") (pinfunction "1_1") (pintype "passive"))
      (node (ref "C39") (pin "2") (pinfunction "2_2") (pintype "passive"))
      (node (ref "C4") (pin "2") (pinfunction "2_2") (pintype "passive"))
      (node (ref "C42") (pin "2") (pinfunction "2_2") (pintype "passive"))
      (node (ref "C43") (pin "2") (pinfunction "2_2") (pintype "passive"))
      (node (ref "C5") (pin "2") (pinfunction "2_2") (pintype "passive"))
      (node (ref "C6") (pin "2") (pinfunction "2_2") (pintype "passive"))
      (node (ref "C7") (pin "2") (pinfunction "2_2") (pintype "passive"))
      (node (ref "C8") (pin "2") (pinfunction "2_2") (pintype "passive"))
      (node (ref "C9") (pin "2") (pinfunction "2_2") (pintype "passive"))
      (node (ref "D2") (pin "1") (pinfunction "K_1") (pintype "bidirectional"))
      (node (ref "D3") (pin "2") (pinfunction "GND_2") (pintype "bidirectional"))
      (node (ref "EPD_C1") (pin "1") (pinfunction "1_1") (pintype "passive"))
      (node (ref "EPD_C10") (pin "1") (pinfunction "1_1") (pintype "passive"))
      (node (ref "EPD_C11") (pin "1") (pinfunction "1_1") (pintype "passive"))
      (node (ref "EPD_C12") (pin "1") (pinfunction "1_1") (pintype "passive"))
      (node (ref "EPD_C2") (pin "1") (pinfunction "1_1") (pintype "passive"))
      (node (ref "EPD_C5") (pin "1") (pinfunction "1_1") (pintype "passive"))
      (node (ref "EPD_C6") (pin "1") (pinfunction "1_1") (pintype "passive"))
      (node (ref "EPD_C7") (pin "1") (pinfunction "1_1") (pintype "passive"))
      (node (ref "EPD_C8") (pin "1") (pinfunction "1_1") (pintype "passive"))
      (node (ref "EPD_C9") (pin "1") (pinfunction "1_1") (pintype "passive"))
      (node (ref "IC1") (pin "D2") (pinfunction "GND_D2") (pintype "bidirectional"))
      (node (ref "IC2") (pin "B1") (pinfunction "IN/TRIG_B1") (pintype "bidirectional"))
      (node (ref "IC2") (pin "B3") (pinfunction "GND_B3") (pintype "bidirectional"))
      (node (ref "IC3") (pin "8") (pinfunction "GNDIO_8") (pintype "bidirectional"))
      (node (ref "IC3") (pin "9") (pinfunction "GND_9") (pintype "bidirectional"))
      (node (ref "IC9") (pin "B1") (pinfunction "VSEL_B1") (pintype "bidirectional"))
      (node (ref "IC9") (pin "C1") (pinfunction "AGND_C1") (pintype "bidirectional"))
      (node (ref "IC9") (pin "C2") (pinfunction "PGND_1_C2") (pintype "bidirectional"))
      (node (ref "IC9") (pin "C3") (pinfunction "PGND_2_C3") (pintype "bidirectional"))
      (node (ref "J1") (pin "17") (pinfunction "17_17") (pintype "bidirectional"))
      (node (ref "J1") (pin "8") (pinfunction "8_8") (pintype "bidirectional"))
      (node (ref "J1") (pin "MP1") (pinfunction "MP1_MP1") (pintype "bidirectional"))
      (node (ref "J1") (pin "MP2") (pinfunction "MP2_MP2") (pintype "bidirectional"))
      (node (ref "J2") (pin "3") (pinfunction "3_3") (pintype "bidirectional"))
      (node (ref "J2") (pin "5") (pinfunction "5_5") (pintype "bidirectional"))
      (node (ref "J4") (pin "A12_B1") (pinfunction "GND_A12_B1") (pintype "power_in"))
      (node (ref "J4") (pin "A1_B12") (pinfunction "GND_A1_B12") (pintype "power_in"))
      (node (ref "J4") (pin "SH1") (pinfunction "SHIELD_SH1") (pintype "passive"))
      (node (ref "J4") (pin "SH2") (pinfunction "SHIELD_SH2") (pintype "passive"))
      (node (ref "J4") (pin "SH3") (pinfunction "SHIELD_SH3") (pintype "passive"))
      (node (ref "J4") (pin "SH4") (pinfunction "SHIELD_SH4") (pintype "passive"))
      (node (ref "R1_USB") (pin "1") (pinfunction "1_1") (pintype "bidirectional"))
      (node (ref "R2_EP_DR") (pin "1") (pinfunction "1_1") (pintype "bidirectional"))
      (node (ref "R2_USB") (pin "2") (pinfunction "2_2") (pintype "bidirectional"))
      (node (ref "R3") (pin "1") (pinfunction "1_1") (pintype "bidirectional"))
      (node (ref "R9") (pin "1") (pinfunction "1_1") (pintype "bidirectional"))
      (node (ref "R_TYPE_SEL") (pin "1") (pinfunction "1_1") (pintype "bidirectional"))
      (node (ref "SJ1") (pin "1") (pinfunction "1_1") (pintype "passive"))
      (node (ref "SW_DN") (pin "1") (pinfunction "1_1") (pintype "passive"))
      (node (ref "SW_ENT") (pin "1") (pinfunction "1_1") (pintype "passive"))
      (node (ref "SW_UP") (pin "1") (pinfunction "1_1") (pintype "passive"))
      (node (ref "TP6") (pin "TP") (pinfunction "TP_TP") (pintype "input"))
      (node (ref "TP_BAT_GND") (pin "TP") (pinfunction "TP_TP") (pintype "input"))
      (node (ref "U1") (pin "P$74") (pinfunction "VSS_PAD_P$74") (pintype "bidirectional"))
      (node (ref "U1") (pin "P$75") (pinfunction "VSS_PAD_P$75") (pintype "bidirectional"))
      (node (ref "U1") (pin "P$76") (pinfunction "VSS_PAD_P$76") (pintype "bidirectional"))
      (node (ref "U1") (pin "P$77") (pinfunction "VSS_PAD_P$77") (pintype "bidirectional"))
      (node (ref "U1") (pin "P$78") (pinfunction "VSS_PAD_P$78") (pintype "bidirectional"))
      (node (ref "U1") (pin "P$79") (pinfunction "VSS_PAD_P$79") (pintype "bidirectional"))
      (node (ref "U1") (pin "P$80") (pinfunction "VSS_PAD_P$80") (pintype "bidirectional"))
      (node (ref "U1") (pin "P$81") (pinfunction "VSS_PAD_P$81") (pintype "bidirectional"))
      (node (ref "U1") (pin "P$82") (pinfunction "VSS_PAD_P$82") (pintype "bidirectional"))
      (node (ref "U1") (pin "P$83") (pinfunction "VSS_PAD_P$83") (pintype "bidirectional"))
      (node (ref "U1") (pin "P$84") (pinfunction "VSS_PAD_P$84") (pintype "bidirectional"))
      (node (ref "U1") (pin "P$85") (pinfunction "VSS_PAD_P$85") (pintype "bidirectional"))
      (node (ref "U1") (pin "P$86") (pinfunction "VSS_PAD_P$86") (pintype "bidirectional"))
      (node (ref "U1") (pin "P$87") (pinfunction "VSS_PAD_P$87") (pintype "bidirectional"))
      (node (ref "U1") (pin "P$88") (pinfunction "VSS_PAD_P$88") (pintype "bidirectional"))
      (node (ref "U1") (pin "P$89") (pinfunction "VSS_PAD_P$89") (pintype "bidirectional"))
      (node (ref "U1") (pin "P$90") (pinfunction "VSS_PAD_P$90") (pintype "bidirectional"))
      (node (ref "U1") (pin "P$B7") (pinfunction "VSS_P$B7") (pintype "power_in"))
      (node (ref "U1") (pin "P$F23") (pinfunction "VSS_PA_P$F23") (pintype "bidirectional"))
      (node (ref "U3") (pin "1") (pinfunction "CTG_1") (pintype "power_in"))
      (node (ref "U3") (pin "4") (pinfunction "GND_4") (pintype "power_in"))
      (node (ref "U3") (pin "6") (pinfunction "QSTRT_6") (pintype "input"))
      (node (ref "U3") (pin "9") (pinfunction "EP_9") (pintype "power_in"))
      (node (ref "X1") (pin "2") (pinfunction "2_2") (pintype "passive"))
      (node (ref "X1") (pin "4") (pinfunction "4_4") (pintype "passive"))
    )
    (net (code "14") (name "HAPTIC_EN") (class "Default")
      (node (ref "IC2") (pin "A1") (pinfunction "EN_A1") (pintype "bidirectional"))
      (node (ref "U1") (pin "P$U1") (pinfunction "P0.12_P$U1") (pintype "bidirectional"))
    )
    (net (code "15") (name "IMU_INT1") (class "Default")
      (node (ref "IC3") (pin "5") (pinfunction "INT1_5") (pintype "bidirectional"))
      (node (ref "U1") (pin "P$N1") (pinfunction "P0.08_P$N1") (pintype "bidirectional"))
    )
    (net (code "16") (name "IMU_INT2") (class "Default")
      (node (ref "IC3") (pin "6") (pinfunction "INT2_6") (pintype "bidirectional"))
      (node (ref "U1") (pin "P$P2") (pinfunction "P1.08_P$P2") (pintype "bidirectional"))
    )
    (net (code "17") (name "LX1") (class "Default")
      (node (ref "IC9") (pin "B2") (pinfunction "SW1_1_B2") (pintype "bidirectional"))
      (node (ref "IC9") (pin "B3") (pinfunction "SW1_2_B3") (pintype "bidirectional"))
      (node (ref "L7") (pin "1") (pinfunction "1_1") (pintype "bidirectional"))
    )
    (net (code "18") (name "LX2") (class "Default")
      (node (ref "IC9") (pin "D2") (pinfunction "SW2_1_D2") (pintype "bidirectional"))
      (node (ref "IC9") (pin "D3") (pinfunction "SW2_2_D3") (pintype "bidirectional"))
      (node (ref "L7") (pin "2") (pinfunction "2_2") (pintype "bidirectional"))
    )
    (net (code "19") (name "MOSI") (class "Default")
      (node (ref "J1") (pin "14") (pinfunction "14_14") (pintype "bidirectional"))
      (node (ref "U1") (pin "P$B13") (pinfunction "P0.03/AIN1_P$B13") (pintype "bidirectional"))
    )
    (net (code "20") (name "Net-(ANT1-FEED)") (class "Default")
      (node (ref "ANT1") (pin "1") (pinfunction "FEED_1") (pintype "input"))
      (node (ref "C22") (pin "1") (pinfunction "1_1") (pintype "passive"))
      (node (ref "C4") (pin "1") (pinfunction "1_1") (pintype "passive"))
      (node (ref "L1") (pin "2") (pinfunction "2_2") (pintype "passive"))
    )
    (net (code "21") (name "Net-(D2-A)") (class "Default")
      (node (ref "C2-EP-DR1") (pin "1") (pinfunction "1_1") (pintype "passive"))
      (node (ref "D2") (pin "2") (pinfunction "A_2") (pintype "bidirectional"))
      (node (ref "D4") (pin "1") (pinfunction "K_1") (pintype "bidirectional"))
    )
    (net (code "22") (name "Net-(D5-A)") (class "Default")
      (node (ref "C2-EP-DR1") (pin "2") (pinfunction "2_2") (pintype "passive"))
      (node (ref "D5") (pin "2") (pinfunction "A_2") (pintype "bidirectional"))
      (node (ref "L5") (pin "1") (pinfunction "1_1") (pintype "passive"))
      (node (ref "Q3") (pin "3") (pinfunction "D_3") (pintype "bidirectional"))
    )
    (net (code "23") (name "Net-(EPD_C1-Pad2)") (class "Default")
      (node (ref "EPD_C1") (pin "2") (pinfunction "2_2") (pintype "passive"))
      (node (ref "J1") (pin "5") (pinfunction "5_5") (pintype "bidirectional"))
    )
    (net (code "24") (name "Net-(EPD_C2-Pad2)") (class "Default")
      (node (ref "EPD_C2") (pin "2") (pinfunction "2_2") (pintype "passive"))
      (node (ref "J1") (pin "4") (pinfunction "4_4") (pintype "bidirectional"))
    )
    (net (code "25") (name "Net-(EPD_C6-Pad2)") (class "Default")
      (node (ref "EPD_C6") (pin "2") (pinfunction "2_2") (pintype "passive"))
      (node (ref "J1") (pin "18") (pinfunction "18_18") (pintype "bidirectional"))
    )
    (net (code "26") (name "Net-(EPD_C7-Pad2)") (class "Default")
      (node (ref "EPD_C7") (pin "2") (pinfunction "2_2") (pintype "passive"))
      (node (ref "J1") (pin "19") (pinfunction "19_19") (pintype "bidirectional"))
    )
    (net (code "27") (name "Net-(EPD_C8-Pad2)") (class "Default")
      (node (ref "EPD_C8") (pin "2") (pinfunction "2_2") (pintype "passive"))
      (node (ref "J1") (pin "20") (pinfunction "20_20") (pintype "bidirectional"))
    )
    (net (code "28") (name "Net-(EPD_C11-Pad2)") (class "Default")
      (node (ref "EPD_C11") (pin "2") (pinfunction "2_2") (pintype "passive"))
      (node (ref "J1") (pin "23") (pinfunction "23_23") (pintype "bidirectional"))
    )
    (net (code "29") (name "Net-(EPD_C12-Pad2)") (class "Default")
      (node (ref "EPD_C12") (pin "2") (pinfunction "2_2") (pintype "passive"))
      (node (ref "J1") (pin "24") (pinfunction "24_24") (pintype "bidirectional"))
    )
    (net (code "30") (name "Net-(IC1-TS{slash}MR)") (class "Default")
      (node (ref "IC1") (pin "D1") (pinfunction "TS/MR_D1") (pintype "bidirectional"))
      (node (ref "R9") (pin "2") (pinfunction "2_2") (pintype "bidirectional"))
    )
    (net (code "31") (name "Net-(IC2-REG)") (class "Default")
      (node (ref "C32") (pin "2") (pinfunction "2_2") (pintype "passive"))
      (node (ref "IC2") (pin "A2") (pinfunction "REG_A2") (pintype "bidirectional"))
    )
    (net (code "32") (name "Net-(IC3-SDO)") (class "Default")
      (node (ref "IC3") (pin "1") (pinfunction "SDO_1") (pintype "bidirectional"))
      (node (ref "R3") (pin "2") (pinfunction "2_2") (pintype "bidirectional"))
    )
    (net (code "33") (name "Net-(IC9-SCL)") (class "Default")
      (node (ref "IC9") (pin "D1") (pinfunction "SCL_D1") (pintype "bidirectional"))
      (node (ref "R4") (pin "2") (pinfunction "2_2") (pintype "bidirectional"))
    )
    (net (code "34") (name "Net-(IC9-SDA)") (class "Default")
      (node (ref "IC9") (pin "E1") (pinfunction "SDA_E1") (pintype "bidirectional"))
      (node (ref "R2") (pin "2") (pinfunction "2_2") (pintype "bidirectional"))
    )
    (net (code "35") (name "Net-(J4-CC1)") (class "Default")
      (node (ref "J4") (pin "A5") (pinfunction "CC1_A5") (pintype "bidirectional"))
      (node (ref "R1_USB") (pin "2") (pinfunction "2_2") (pintype "bidirectional"))
    )
    (net (code "36") (name "Net-(J4-CC2)") (class "Default")
      (node (ref "J4") (pin "B5") (pinfunction "CC2_B5") (pintype "bidirectional"))
      (node (ref "R2_USB") (pin "1") (pinfunction "1_1") (pintype "bidirectional"))
    )
    (net (code "37") (name "Net-(L2-Pad1)") (class "Default")
      (node (ref "L2") (pin "1") (pinfunction "1_1") (pintype "passive"))
      (node (ref "L3") (pin "2") (pinfunction "2_2") (pintype "passive"))
    )
    (net (code "38") (name "Net-(R1_EP_DR-Pad1)") (class "Default")
      (node (ref "R1_EP_DR") (pin "1") (pinfunction "1_1") (pintype "bidirectional"))
      (node (ref "R_TYPE_SEL") (pin "2") (pinfunction "2_2") (pintype "bidirectional"))
      (node (ref "SJ1") (pin "2") (pinfunction "2_2") (pintype "passive"))
    )
    (net (code "39") (name "Net-(U1-ANT)") (class "Default")
      (node (ref "C3") (pin "1") (pinfunction "1_1") (pintype "passive"))
      (node (ref "L1") (pin "1") (pinfunction "1_1") (pintype "passive"))
      (node (ref "U1") (pin "P$H23") (pinfunction "ANT_P$H23") (pintype "bidirectional"))
    )
    (net (code "40") (name "Net-(U1-DCC)") (class "Default")
      (node (ref "L2") (pin "2") (pinfunction "2_2") (pintype "passive"))
      (node (ref "U1") (pin "P$B3") (pinfunction "DCC_P$B3") (pintype "output"))
    )
    (net (code "41") (name "Net-(U1-DEC1)") (class "Default")
      (node (ref "C5") (pin "1") (pinfunction "1_1") (pintype "passive"))
      (node (ref "U1") (pin "P$C1") (pinfunction "DEC1_P$C1") (pintype "power_in"))
    )
    (net (code "42") (name "Net-(U1-DEC2)") (class "Default")
      (node (ref "C13") (pin "2") (pinfunction "2_2") (pintype "passive"))
      (node (ref "U1") (pin "P$A18") (pinfunction "DEC2_P$A18") (pintype "bidirectional"))
    )
    (net (code "43") (name "Net-(U1-DEC3)") (class "Default")
      (node (ref "C11") (pin "1") (pinfunction "1_1") (pintype "passive"))
      (node (ref "U1") (pin "P$D23") (pinfunction "DEC3_P$D23") (pintype "bidirectional"))
    )
    (net (code "44") (name "Net-(U1-DEC3V3)") (class "Default")
      (node (ref "C20") (pin "1") (pinfunction "1_1") (pintype "passive"))
      (node (ref "U1") (pin "P$AC5") (pinfunction "DEC3V3_P$AC5") (pintype "bidirectional"))
    )
    (net (code "45") (name "Net-(U1-DEC4)") (class "Default")
      (node (ref "C10") (pin "2") (pinfunction "2_2") (pintype "passive"))
      (node (ref "C15") (pin "1") (pinfunction "1_1") (pintype "passive"))
      (node (ref "C16") (pin "1") (pinfunction "1_1") (pintype "passive"))
      (node (ref "L3") (pin "1") (pinfunction "1_1") (pintype "passive"))
      (node (ref "U1") (pin "P$B5") (pinfunction "DEC4_P$B5") (pintype "power_in"))
      (node (ref "U1") (pin "P$E24") (pinfunction "DEC6_P$E24") (pintype "bidirectional"))
    )
    (net (code "46") (name "Net-(U1-DEC5)") (class "Default")
      (node (ref "C9") (pin "1") (pinfunction "1_1") (pintype "passive"))
      (node (ref "U1") (pin "P$N24") (pinfunction "DEC5_P$N24") (pintype "bidirectional"))
    )
    (net (code "47") (name "Net-(U1-P0.00{slash}XL1)") (class "Default")
      (node (ref "C17") (pin "2") (pinfunction "2_2") (pintype "passive"))
      (node (ref "U1") (pin "P$D2") (pinfunction "P0.00/XL1_P$D2") (pintype "bidirectional"))
      (node (ref "X2") (pin "2") (pinfunction "2_2") (pintype "passive"))
    )
    (net (code "48") (name "Net-(U1-P0.01{slash}XL2)") (class "Default")
      (node (ref "C18") (pin "2") (pinfunction "2_2") (pintype "passive"))
      (node (ref "U1") (pin "P$F2") (pinfunction "P0.01/XL2_P$F2") (pintype "bidirectional"))
      (node (ref "X2") (pin "1") (pinfunction "1_1") (pintype "passive"))
    )
    (net (code "49") (name "Net-(U1-XC1)") (class "Default")
      (node (ref "C1") (pin "1") (pinfunction "1_1") (pintype "passive"))
      (node (ref "U1") (pin "P$B24") (pinfunction "XC1_P$B24") (pintype "input"))
      (node (ref "X1") (pin "1") (pinfunction "1_1") (pintype "passive"))
    )
    (net (code "50") (name "Net-(U1-XC2)") (class "Default")
      (node (ref "C2") (pin "1") (pinfunction "1_1") (pintype "passive"))
      (node (ref "U1") (pin "P$A23") (pinfunction "XC2_P$A23") (pintype "output"))
      (node (ref "X1") (pin "3") (pinfunction "3_3") (pintype "passive"))
    )
    (net (code "51") (name "OUT+") (class "Default")
      (node (ref "IC2") (pin "A3") (pinfunction "OUT+_A3") (pintype "bidirectional"))
      (node (ref "TP_OP") (pin "TP") (pinfunction "TP_TP") (pintype "input"))
    )
    (net (code "52") (name "OUT-") (class "Default")
      (node (ref "IC2") (pin "C3") (pinfunction "OUT-_C3") (pintype "bidirectional"))
      (node (ref "TP_ON") (pin "TP") (pinfunction "TP_TP") (pintype "input"))
    )
    (net (code "53") (name "P0.04") (class "Default")
      (node (ref "U1") (pin "P$J1") (pinfunction "P0.04/AIN2_P$J1") (pintype "bidirectional"))
    )
    (net (code "54") (name "P0.09") (class "Default")
      (node (ref "U1") (pin "P$L24") (pinfunction "P0.09/NFC1_P$L24") (pintype "bidirectional"))
    )
    (net (code "55") (name "P0.13") (class "Default")
      (node (ref "C30") (pin "1") (pinfunction "1_1") (pintype "passive"))
      (node (ref "R5") (pin "1") (pinfunction "1_1") (pintype "bidirectional"))
      (node (ref "SW_UP") (pin "2") (pinfunction "2_2") (pintype "passive"))
      (node (ref "U1") (pin "P$AD8") (pinfunction "P0.13_P$AD8") (pintype "bidirectional"))
    )
    (net (code "56") (name "P0.14") (class "Default")
      (node (ref "C31") (pin "1") (pinfunction "1_1") (pintype "passive"))
      (node (ref "R8") (pin "1") (pinfunction "1_1") (pintype "bidirectional"))
      (node (ref "SW_ENT") (pin "2") (pinfunction "2_2") (pintype "passive"))
      (node (ref "U1") (pin "P$AC9") (pinfunction "P0.14_P$AC9") (pintype "bidirectional"))
    )
    (net (code "57") (name "P0.19") (class "Default")
      (node (ref "U1") (pin "P$AC15") (pinfunction "P0.19_P$AC15") (pintype "bidirectional"))
    )
    (net (code "58") (name "P0.20") (class "Default")
      (node (ref "U1") (pin "P$AD16") (pinfunction "P0.20_P$AD16") (pintype "bidirectional"))
    )
    (net (code "59") (name "P0.21") (class "Default")
      (node (ref "U1") (pin "P$AC17") (pinfunction "P0.21_P$AC17") (pintype "bidirectional"))
    )
    (net (code "60") (name "P0.22") (class "Default")
      (node (ref "U1") (pin "P$AD18") (pinfunction "P0.22_P$AD18") (pintype "bidirectional"))
    )
    (net (code "61") (name "P0.23") (class "Default")
      (node (ref "U1") (pin "P$AC19") (pinfunction "P0.23_P$AC19") (pintype "bidirectional"))
    )
    (net (code "62") (name "P0.24") (class "Default")
      (node (ref "U1") (pin "P$AD20") (pinfunction "P0.24_P$AD20") (pintype "bidirectional"))
    )
    (net (code "63") (name "P0.25") (class "Default")
      (node (ref "U1") (pin "P$AC21") (pinfunction "P0.25_P$AC21") (pintype "bidirectional"))
    )
    (net (code "64") (name "P0.26") (class "Default")
      (node (ref "U1") (pin "P$G1") (pinfunction "P0.26_P$G1") (pintype "bidirectional"))
    )
    (net (code "65") (name "P0.27") (class "Default")
      (node (ref "U1") (pin "P$H2") (pinfunction "P0.27_P$H2") (pintype "bidirectional"))
    )
    (net (code "66") (name "P0.28") (class "Default")
      (node (ref "U1") (pin "P$B11") (pinfunction "P0.28/AIN4_P$B11") (pintype "bidirectional"))
    )
    (net (code "67") (name "P0.29") (class "Default")
      (node (ref "U1") (pin "P$A10") (pinfunction "P0.29/AIN5_P$A10") (pintype "bidirectional"))
    )
    (net (code "68") (name "P0.30") (class "Default")
      (node (ref "U1") (pin "P$B9") (pinfunction "P0.30/AIN6_P$B9") (pintype "bidirectional"))
    )
    (net (code "69") (name "P0.31") (class "Default")
      (node (ref "U1") (pin "P$A8") (pinfunction "P0.31/AIN7_P$A8") (pintype "bidirectional"))
    )
    (net (code "70") (name "P1.01") (class "Default")
      (node (ref "Q1") (pin "1") (pinfunction "G_1") (pintype "bidirectional"))
      (node (ref "R_PWR_EPD") (pin "1") (pinfunction "1_1") (pintype "bidirectional"))
      (node (ref "U1") (pin "P$Y23") (pinfunction "P1.01_P$Y23") (pintype "bidirectional"))
    )
    (net (code "71") (name "P1.02") (class "Default")
      (node (ref "C29") (pin "1") (pinfunction "1_1") (pintype "passive"))
      (node (ref "R7") (pin "1") (pinfunction "1_1") (pintype "bidirectional"))
      (node (ref "SW_DN") (pin "2") (pinfunction "2_2") (pintype "passive"))
      (node (ref "U1") (pin "P$W24") (pinfunction "P1.02_P$W24") (pintype "bidirectional"))
    )
    (net (code "72") (name "P1.03") (class "Default")
      (node (ref "U1") (pin "P$V23") (pinfunction "P1.03_P$V23") (pintype "bidirectional"))
    )
    (net (code "73") (name "P1.04") (class "Default")
      (node (ref "U1") (pin "P$U24") (pinfunction "P1.04_P$U24") (pintype "bidirectional"))
    )
    (net (code "74") (name "P1.05") (class "Default")
      (node (ref "U1") (pin "P$T23") (pinfunction "P1.05_P$T23") (pintype "bidirectional"))
    )
    (net (code "75") (name "P1.06") (class "Default")
      (node (ref "U1") (pin "P$R24") (pinfunction "P1.06_P$R24") (pintype "bidirectional"))
    )
    (net (code "76") (name "P1.07") (class "Default")
      (node (ref "U1") (pin "P$P23") (pinfunction "P1.07_P$P23") (pintype "bidirectional"))
    )
    (net (code "77") (name "P1.09") (class "Default")
      (node (ref "U1") (pin "P$R1") (pinfunction "P1.09_P$R1") (pintype "bidirectional"))
    )
    (net (code "78") (name "P1.10") (class "Default")
      (node (ref "U1") (pin "P$A20") (pinfunction "P1.10_P$A20") (pintype "bidirectional"))
    )
    (net (code "79") (name "P1.11") (class "Default")
      (node (ref "U1") (pin "P$B19") (pinfunction "P1.11_P$B19") (pintype "bidirectional"))
    )
    (net (code "80") (name "P1.12") (class "Default")
      (node (ref "U1") (pin "P$B17") (pinfunction "P1.12_P$B17") (pintype "bidirectional"))
    )
    (net (code "81") (name "P1.13") (class "Default")
      (node (ref "U1") (pin "P$A16") (pinfunction "P1.13_P$A16") (pintype "bidirectional"))
    )
    (net (code "82") (name "P1.14") (class "Default")
      (node (ref "U1") (pin "P$B15") (pinfunction "P1.14_P$B15") (pintype "bidirectional"))
    )
    (net (code "83") (name "P1.15") (class "Default")
      (node (ref "U1") (pin "P$A14") (pinfunction "P1.15_P$A14") (pintype "bidirectional"))
    )
    (net (code "84") (name "PMIC_INT") (class "Default")
      (node (ref "IC1") (pin "A1") (pinfunction "~{INT}_A1") (pintype "bidirectional"))
      (node (ref "U1") (pin "P$T2") (pinfunction "P0.11_P$T2") (pintype "bidirectional"))
    )
    (net (code "85") (name "PREVGH") (class "Default")
      (node (ref "D5") (pin "1") (pinfunction "K_1") (pintype "bidirectional"))
      (node (ref "EPD_C9") (pin "2") (pinfunction "2_2") (pintype "passive"))
      (node (ref "J1") (pin "21") (pinfunction "21_21") (pintype "bidirectional"))
    )
    (net (code "86") (name "PREVGL") (class "Default")
      (node (ref "D4") (pin "2") (pinfunction "A_2") (pintype "bidirectional"))
      (node (ref "EPD_C10") (pin "2") (pinfunction "2_2") (pintype "passive"))
      (node (ref "J1") (pin "22") (pinfunction "22_22") (pintype "bidirectional"))
    )
    (net (code "87") (name "RESE") (class "Default")
      (node (ref "J1") (pin "3") (pinfunction "3_3") (pintype "bidirectional"))
      (node (ref "Q3") (pin "2") (pinfunction "S_2") (pintype "bidirectional"))
      (node (ref "R1_EP_DR") (pin "2") (pinfunction "2_2") (pintype "bidirectional"))
    )
    (net (code "88") (name "RESET") (class "Default")
      (node (ref "J2") (pin "6") (pinfunction "6_6") (pintype "bidirectional"))
      (node (ref "TP4") (pin "TP") (pinfunction "TP_TP") (pintype "input"))
      (node (ref "U1") (pin "P$AC13") (pinfunction "P0.18/RESET_P$AC13") (pintype "bidirectional"))
    )
    (net (code "89") (name "SCK") (class "Default")
      (node (ref "J1") (pin "13") (pinfunction "13_13") (pintype "bidirectional"))
      (node (ref "U1") (pin "P$A12") (pinfunction "P0.02/AIN0_P$A12") (pintype "bidirectional"))
    )
    (net (code "90") (name "SCL") (class "Default")
      (node (ref "IC1") (pin "B1") (pinfunction "SCL_B1") (pintype "bidirectional"))
      (node (ref "IC2") (pin "C1") (pinfunction "SCL_C1") (pintype "bidirectional"))
      (node (ref "IC3") (pin "12") (pinfunction "SCX_12") (pintype "bidirectional"))
      (node (ref "R17") (pin "2") (pinfunction "2_2") (pintype "bidirectional"))
      (node (ref "R4") (pin "1") (pinfunction "1_1") (pintype "bidirectional"))
      (node (ref "TP_SCL") (pin "TP") (pinfunction "TP_TP") (pintype "input"))
      (node (ref "U1") (pin "P$M2") (pinfunction "P0.07_P$M2") (pintype "bidirectional"))
      (node (ref "U3") (pin "7") (pinfunction "SCL_7") (pintype "input"))
    )
    (net (code "91") (name "SDA") (class "Default")
      (node (ref "IC1") (pin "C1") (pinfunction "SDA_C1") (pintype "bidirectional"))
      (node (ref "IC2") (pin "B2") (pinfunction "SDA_B2") (pintype "bidirectional"))
      (node (ref "IC3") (pin "2") (pinfunction "SDX_2") (pintype "bidirectional"))
      (node (ref "R18") (pin "2") (pinfunction "2_2") (pintype "bidirectional"))
      (node (ref "R2") (pin "1") (pinfunction "1_1") (pintype "bidirectional"))
      (node (ref "TP_SDA") (pin "TP") (pinfunction "TP_TP") (pintype "input"))
      (node (ref "U1") (pin "P$L1") (pinfunction "P0.06_P$L1") (pintype "bidirectional"))
      (node (ref "U3") (pin "8") (pinfunction "SDA_8") (pintype "bidirectional"))
    )
    (net (code "92") (name "SWDCLK") (class "Default")
      (node (ref "J2") (pin "4") (pinfunction "4_4") (pintype "bidirectional"))
      (node (ref "TP3") (pin "TP") (pinfunction "TP_TP") (pintype "input"))
      (node (ref "U1") (pin "P$AA24") (pinfunction "SWDCLK_P$AA24") (pintype "input"))
    )
    (net (code "93") (name "SWDIO") (class "Default")
      (node (ref "J2") (pin "2") (pinfunction "2_2") (pintype "bidirectional"))
      (node (ref "TP2") (pin "TP") (pinfunction "TP_TP") (pintype "input"))
      (node (ref "U1") (pin "P$AC24") (pinfunction "SWDIO_P$AC24") (pintype "bidirectional"))
    )
    (net (code "94") (name "SWO") (class "Default")
      (node (ref "TP1") (pin "TP") (pinfunction "TP_TP") (pintype "input"))
      (node (ref "U1") (pin "P$AD22") (pinfunction "P1.00_P$AD22") (pintype "bidirectional"))
    )
    (net (code "95") (name "VBAT") (class "Default")
      (node (ref "C27") (pin "1") (pinfunction "1_1") (pintype "passive"))
      (node (ref "C37") (pin "2") (pinfunction "2_2") (pintype "passive"))
      (node (ref "IC1") (pin "C2") (pinfunction "BAT_C2") (pintype "bidirectional"))
      (node (ref "TP_VBAT") (pin "TP") (pinfunction "TP_TP") (pintype "input"))
      (node (ref "U3") (pin "2") (pinfunction "CELL_2") (pintype "power_in"))
      (node (ref "U3") (pin "3") (pinfunction "VDD_3") (pintype "power_in"))
    )
    (net (code "96") (name "VBUS") (class "Default")
      (node (ref "C21") (pin "1") (pinfunction "1_1") (pintype "passive"))
      (node (ref "C38") (pin "2") (pinfunction "2_2") (pintype "passive"))
      (node (ref "C42") (pin "1") (pinfunction "1_1") (pintype "passive"))
      (node (ref "C43") (pin "1") (pinfunction "1_1") (pintype "passive"))
      (node (ref "D3") (pin "5") (pinfunction "VBUS_5") (pintype "bidirectional"))
      (node (ref "IC1") (pin "A2") (pinfunction "IN_A2") (pintype "bidirectional"))
      (node (ref "J4") (pin "A4_B9") (pinfunction "VBUS_A4_B9") (pintype "power_in"))
      (node (ref "J4") (pin "A9_B4") (pinfunction "VBUS_A9_B4") (pintype "power_in"))
      (node (ref "U1") (pin "P$AD2") (pinfunction "VBUS_P$AD2") (pintype "power_in"))
    )
    (net (code "97") (name "VREG") (class "Default")
      (node (ref "C23") (pin "2") (pinfunction "2_2") (pintype "passive"))
      (node (ref "C24") (pin "2") (pinfunction "2_2") (pintype "passive"))
      (node (ref "C39") (pin "1") (pinfunction "1_1") (pintype "passive"))
      (node (ref "IC1") (pin "B2") (pinfunction "SYS_B2") (pintype "bidirectional"))
      (node (ref "IC9") (pin "A1") (pinfunction "EN_A1") (pintype "bidirectional"))
      (node (ref "IC9") (pin "A2") (pinfunction "VIN_1_A2") (pintype "bidirectional"))
      (node (ref "IC9") (pin "A3") (pinfunction "VIN_2_A3") (pintype "bidirectional"))
      (node (ref "TP_VREG") (pin "TP") (pinfunction "TP_TP") (pintype "input"))
    )
    (net (code "98") (name "unconnected-(ANT1-NC-Pad2)") (class "Default")
      (node (ref "ANT1") (pin "2") (pinfunction "NC_2") (pintype "no_connect"))
    )
    (net (code "99") (name "unconnected-(IC3-ASCL-Pad11)") (class "Default")
      (node (ref "IC3") (pin "11") (pinfunction "ASCL_11") (pintype "bidirectional"))
    )
    (net (code "100") (name "unconnected-(IC3-ASDA-Pad4)") (class "Default")
      (node (ref "IC3") (pin "4") (pinfunction "ASDA_4") (pintype "bidirectional"))
    )
    (net (code "101") (name "unconnected-(J1-Pad1)") (class "Default")
      (node (ref "J1") (pin "1") (pinfunction "1_1") (pintype "bidirectional"))
    )
    (net (code "102") (name "unconnected-(J1-Pad6)") (class "Default")
      (node (ref "J1") (pin "6") (pinfunction "6_6") (pintype "bidirectional"))
    )
    (net (code "103") (name "unconnected-(J1-Pad7)") (class "Default")
      (node (ref "J1") (pin "7") (pinfunction "7_7") (pintype "bidirectional"))
    )
    (net (code "104") (name "unconnected-(J4-SBU1-PadA8)") (class "Default")
      (node (ref "J4") (pin "A8") (pinfunction "SBU1_A8") (pintype "bidirectional"))
    )
    (net (code "105") (name "unconnected-(J4-SBU2-PadB8)") (class "Default")
      (node (ref "J4") (pin "B8") (pinfunction "SBU2_B8") (pintype "bidirectional"))
    )
    (net (code "106") (name "unconnected-(U1-DCCH-PadP$AB2)") (class "Default")
      (node (ref "U1") (pin "P$AB2") (pinfunction "DCCH_P$AB2") (pintype "bidirectional"))
    )
  )
)
